# 2_DotexBoard_ENC28J60.net
KiCad netlist of a schematic drawn in Altium Designer
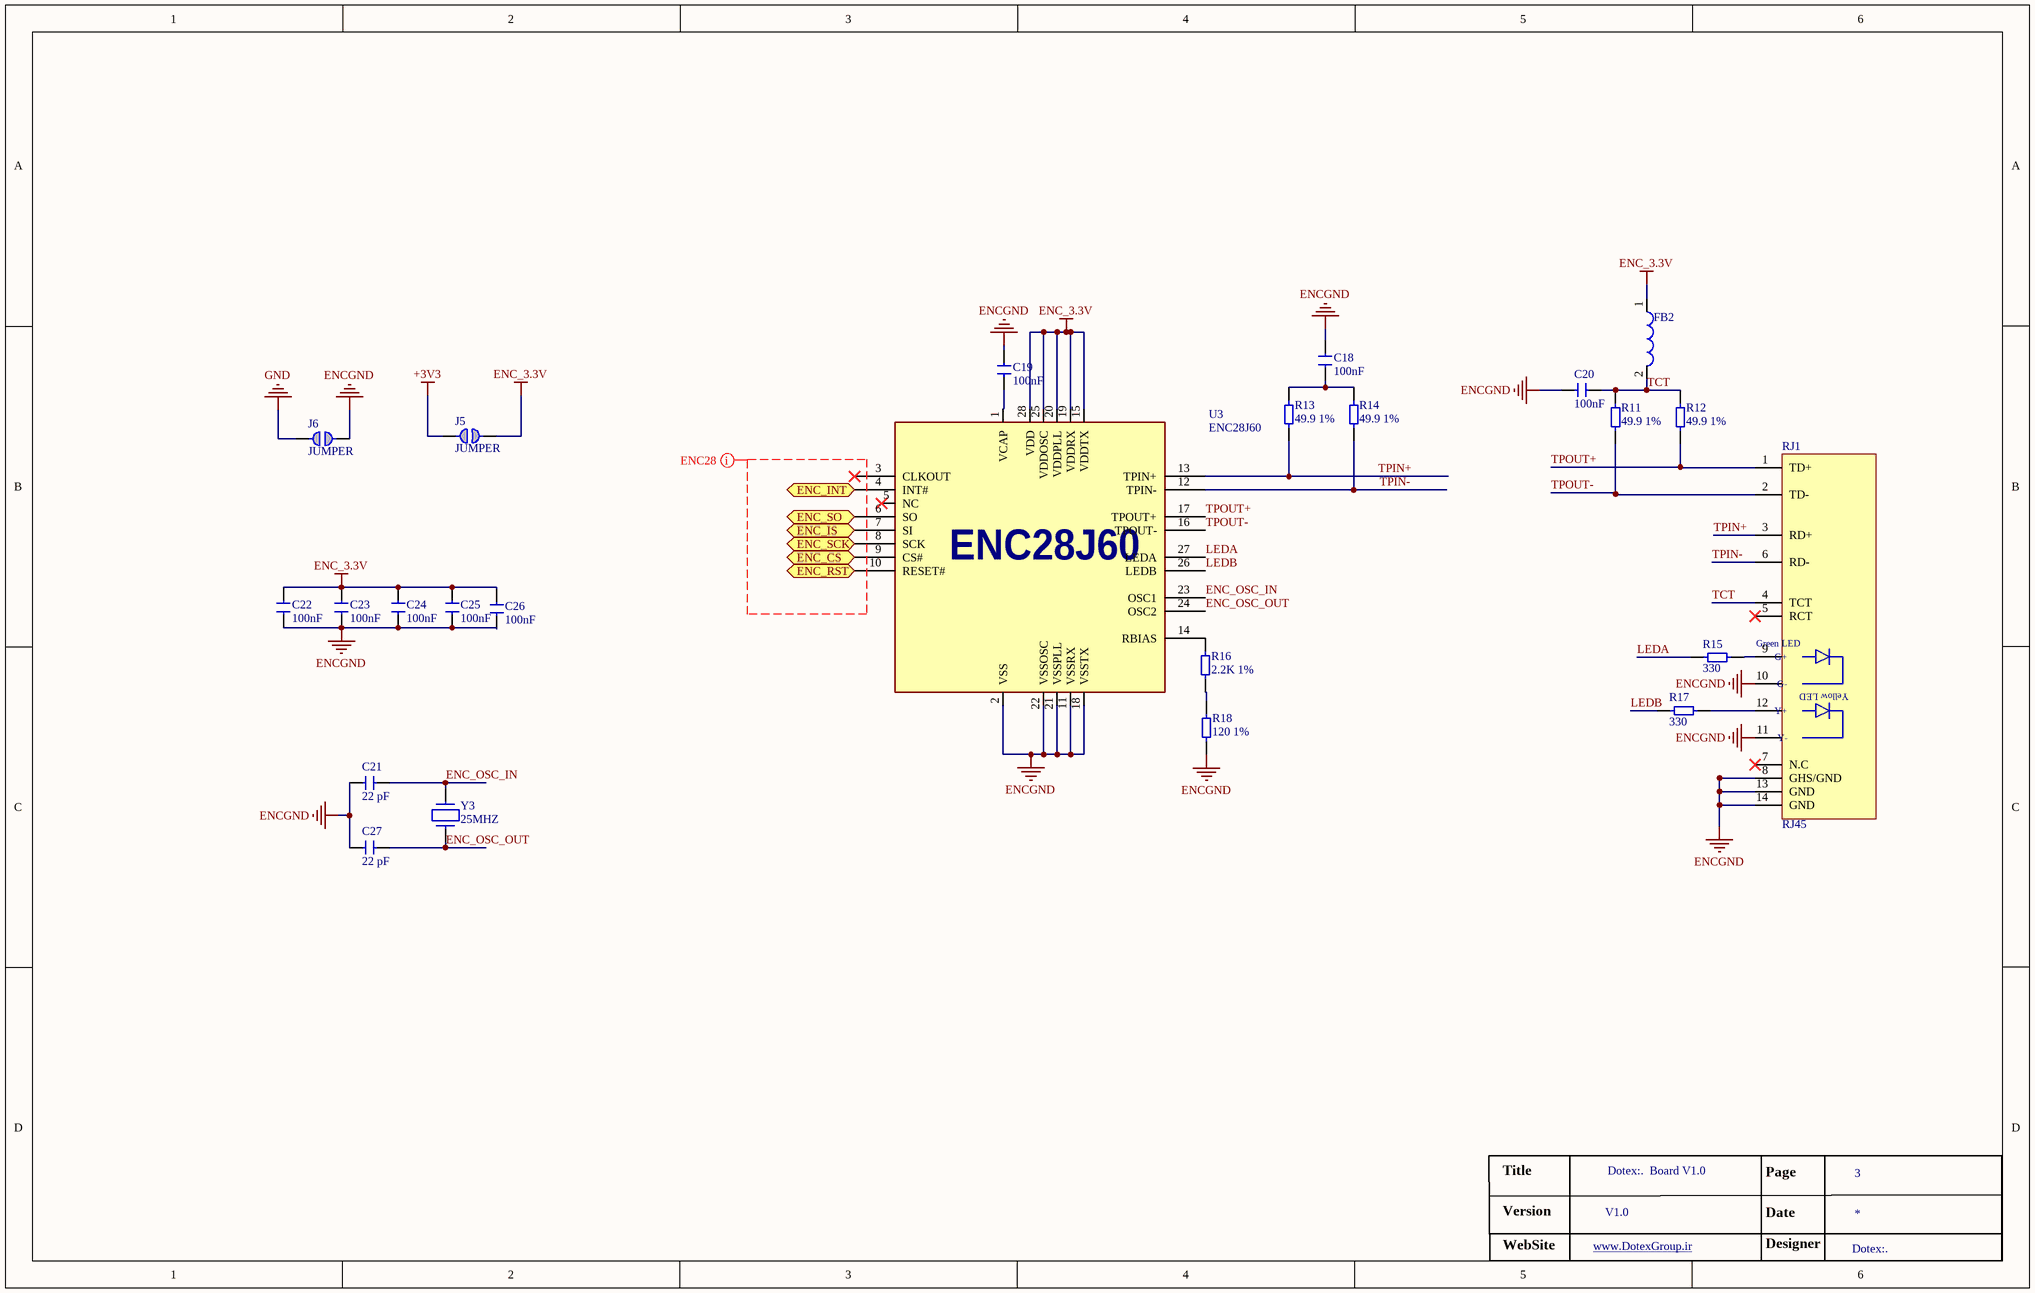
[diagram p0: [2]DotexBoard_ENC28J60.SchDoc]

(export (version "E")
  (design (tool "Eeschema 10.0.6"))
  (components
    (comp (ref "C18")
      (value "Comment")
      (footprint "0805 Capacitor")
      (fields (field (name "ALTIUM_UNNAMED_1") "100nF"))
      (libsource (lib "DotexGroup_LIB") (part "Capacitor SMD"))
    )
    (comp (ref "C19")
      (value "Comment")
      (footprint "0805 Capacitor")
      (fields (field (name "ALTIUM_UNNAMED_1") "100nF"))
      (libsource (lib "DotexGroup_LIB") (part "Capacitor SMD"))
    )
    (comp (ref "C20")
      (value "Comment")
      (footprint "0805 Capacitor")
      (fields (field (name "ALTIUM_UNNAMED_1") "100nF"))
      (libsource (lib "DotexGroup_LIB") (part "Capacitor SMD"))
    )
    (comp (ref "C21")
      (value "Comment")
      (footprint "0805 Capacitor")
      (fields (field (name "ALTIUM_UNNAMED_1") "22 pF"))
      (libsource (lib "DotexGroup_LIB") (part "Capacitor SMD"))
    )
    (comp (ref "C22")
      (value "Comment")
      (footprint "0805 Capacitor")
      (fields (field (name "ALTIUM_UNNAMED_1") "100nF"))
      (libsource (lib "DotexGroup_LIB") (part "Capacitor SMD"))
    )
    (comp (ref "C23")
      (value "Comment")
      (footprint "0805 Capacitor")
      (fields (field (name "ALTIUM_UNNAMED_1") "100nF"))
      (libsource (lib "DotexGroup_LIB") (part "Capacitor SMD"))
    )
    (comp (ref "C24")
      (value "Comment")
      (footprint "0805 Capacitor")
      (fields (field (name "ALTIUM_UNNAMED_1") "100nF"))
      (libsource (lib "DotexGroup_LIB") (part "Capacitor SMD"))
    )
    (comp (ref "C25")
      (value "Comment")
      (footprint "0805 Capacitor")
      (fields (field (name "ALTIUM_UNNAMED_1") "100nF"))
      (libsource (lib "DotexGroup_LIB") (part "Capacitor SMD"))
    )
    (comp (ref "C26")
      (value "Comment")
      (footprint "0805 Capacitor")
      (fields (field (name "ALTIUM_UNNAMED_1") "100nF"))
      (libsource (lib "DotexGroup_LIB") (part "Capacitor SMD"))
    )
    (comp (ref "C27")
      (value "Comment")
      (footprint "0805 Capacitor")
      (fields (field (name "ALTIUM_UNNAMED_1") "22 pF"))
      (libsource (lib "DotexGroup_LIB") (part "Capacitor SMD"))
    )
    (comp (ref "FB2")
      (value "Comment")
      (footprint "0805 Ferrit Bead")
      (libsource (lib "DotexGroup_LIB") (part "Ferrit Bead"))
    )
    (comp (ref "J5")
      (value "JUMPER")
      (footprint "0603 Resistor")
      (libsource (lib "DotexGroup_LIB") (part "jumper SMD"))
    )
    (comp (ref "J6")
      (value "JUMPER")
      (footprint "0603 Resistor")
      (libsource (lib "DotexGroup_LIB") (part "jumper SMD"))
    )
    (comp (ref "R11")
      (value "Comment")
      (footprint "0805 Resistor")
      (fields (field (name "ALTIUM_UNNAMED_1") "49.9 1%"))
      (libsource (lib "DotexGroup_LIB") (part "Resistor SMD"))
    )
    (comp (ref "R12")
      (value "Comment")
      (footprint "0805 Resistor")
      (fields (field (name "ALTIUM_UNNAMED_1") "49.9 1%"))
      (libsource (lib "DotexGroup_LIB") (part "Resistor SMD"))
    )
    (comp (ref "R13")
      (value "Comment")
      (footprint "0805 Resistor")
      (fields (field (name "ALTIUM_UNNAMED_1") "49.9 1%"))
      (libsource (lib "DotexGroup_LIB") (part "Resistor SMD"))
    )
    (comp (ref "R14")
      (value "Comment")
      (footprint "0805 Resistor")
      (fields (field (name "ALTIUM_UNNAMED_1") "49.9 1%"))
      (libsource (lib "DotexGroup_LIB") (part "Resistor SMD"))
    )
    (comp (ref "R15")
      (value "Comment")
      (footprint "0805 Resistor")
      (fields (field (name "ALTIUM_UNNAMED_1") "330"))
      (libsource (lib "DotexGroup_LIB") (part "Resistor SMD"))
    )
    (comp (ref "R16")
      (value "Comment")
      (footprint "0805 Resistor")
      (fields (field (name "ALTIUM_UNNAMED_1") "2.2K 1%"))
      (libsource (lib "DotexGroup_LIB") (part "Resistor SMD"))
    )
    (comp (ref "R17")
      (value "Comment")
      (footprint "0805 Resistor")
      (fields (field (name "ALTIUM_UNNAMED_1") "330"))
      (libsource (lib "DotexGroup_LIB") (part "Resistor SMD"))
    )
    (comp (ref "R18")
      (value "Comment")
      (footprint "0805 Resistor")
      (fields (field (name "ALTIUM_UNNAMED_1") "120 1%"))
      (libsource (lib "DotexGroup_LIB") (part "Resistor SMD"))
    )
    (comp (ref "RJ1")
      (value "RJ45")
      (footprint "HR91105A-RJ45")
      (libsource (lib "DotexGroup_LIB") (part "HR911105A"))
    )
    (comp (ref "U3")
      (value "ENC28J60")
      (footprint "SO_28_W")
      (description "Ethernet Controller, 10/100, MII/RMII")
      (fields (field (name "MANF") "Microchip") (field (name "MANF_P#") "ENC28J60-I/SO, ENC28J60-C/SO"))
      (libsource (lib "DotexGroup_LIB") (part "ENC28J60_SOP"))
    )
    (comp (ref "Y3") (value "25MHZ") (footprint "Xtal 2p") (libsource (lib "DotexGroup_LIB") (part "Xtal")))
  )
  (nets
    (net (code "1") (name "+3V3") (class "Default") (node (ref "J5") (pin "1") (pintype "passive")))
    (net (code "2") (name "/ENC_CS") (class "Default")
      (node (ref "U3") (pin "9") (pinfunction "CS#_9") (pintype "passive"))
    )
    (net (code "3") (name "/ENC_INT") (class "Default")
      (node (ref "U3") (pin "4") (pinfunction "INT#_4") (pintype "passive"))
    )
    (net (code "4") (name "/ENC_IS") (class "Default")
      (node (ref "U3") (pin "7") (pinfunction "SI_7") (pintype "passive"))
    )
    (net (code "5") (name "/ENC_OSC_IN") (class "Default")
      (node (ref "C21") (pin "2") (pintype "passive"))
      (node (ref "U3") (pin "23") (pinfunction "OSC1_23") (pintype "passive"))
      (node (ref "Y3") (pin "2") (pintype "passive"))
    )
    (net (code "6") (name "/ENC_OSC_OUT") (class "Default")
      (node (ref "C27") (pin "1") (pintype "passive"))
      (node (ref "U3") (pin "24") (pinfunction "OSC2_24") (pintype "passive"))
      (node (ref "Y3") (pin "1") (pintype "passive"))
    )
    (net (code "7") (name "/ENC_RST") (class "Default")
      (node (ref "U3") (pin "10") (pinfunction "RESET#_10") (pintype "passive"))
    )
    (net (code "8") (name "/ENC_SCK") (class "Default")
      (node (ref "U3") (pin "8") (pinfunction "SCK_8") (pintype "passive"))
    )
    (net (code "9") (name "/ENC_SO") (class "Default")
      (node (ref "U3") (pin "6") (pinfunction "SO_6") (pintype "passive"))
    )
    (net (code "10") (name "/LEDA") (class "Default")
      (node (ref "R15") (pin "1") (pintype "passive"))
      (node (ref "U3") (pin "27") (pinfunction "LEDA_27") (pintype "passive"))
    )
    (net (code "11") (name "/LEDB") (class "Default")
      (node (ref "R17") (pin "2") (pintype "passive"))
      (node (ref "U3") (pin "26") (pinfunction "LEDB_26") (pintype "passive"))
    )
    (net (code "12") (name "/TCT") (class "Default")
      (node (ref "C20") (pin "1") (pintype "passive"))
      (node (ref "FB2") (pin "2") (pinfunction "2_2") (pintype "passive"))
      (node (ref "R11") (pin "1") (pintype "passive"))
      (node (ref "R12") (pin "1") (pintype "passive"))
      (node (ref "RJ1") (pin "4") (pinfunction "TCT_4") (pintype "passive"))
    )
    (net (code "13") (name "/TPIN+") (class "Default")
      (node (ref "R13") (pin "2") (pintype "passive"))
      (node (ref "RJ1") (pin "3") (pinfunction "RD+_3") (pintype "passive"))
      (node (ref "U3") (pin "13") (pinfunction "TPIN+_13") (pintype "passive"))
    )
    (net (code "14") (name "/TPIN-") (class "Default")
      (node (ref "R14") (pin "2") (pintype "passive"))
      (node (ref "RJ1") (pin "6") (pinfunction "RD-_6") (pintype "passive"))
      (node (ref "U3") (pin "12") (pinfunction "TPIN-_12") (pintype "passive"))
    )
    (net (code "15") (name "/TPOUT+") (class "Default")
      (node (ref "R12") (pin "2") (pintype "passive"))
      (node (ref "RJ1") (pin "1") (pinfunction "TD+_1") (pintype "passive"))
      (node (ref "U3") (pin "17") (pinfunction "TPOUT+_17") (pintype "passive"))
    )
    (net (code "16") (name "/TPOUT-") (class "Default")
      (node (ref "R11") (pin "2") (pintype "passive"))
      (node (ref "RJ1") (pin "2") (pinfunction "TD-_2") (pintype "passive"))
      (node (ref "U3") (pin "16") (pinfunction "TPOUT-_16") (pintype "passive"))
    )
    (net (code "17") (name "ENCGND") (class "Default")
      (node (ref "C18") (pin "1") (pintype "passive"))
      (node (ref "C19") (pin "2") (pintype "passive"))
      (node (ref "C20") (pin "2") (pintype "passive"))
      (node (ref "C21") (pin "1") (pintype "passive"))
      (node (ref "C22") (pin "1") (pintype "passive"))
      (node (ref "C23") (pin "1") (pintype "passive"))
      (node (ref "C24") (pin "1") (pintype "passive"))
      (node (ref "C25") (pin "1") (pintype "passive"))
      (node (ref "C26") (pin "1") (pintype "passive"))
      (node (ref "C27") (pin "2") (pintype "passive"))
      (node (ref "J6") (pin "2") (pintype "passive"))
      (node (ref "R18") (pin "2") (pintype "passive"))
      (node (ref "RJ1") (pin "10") (pintype "passive"))
      (node (ref "RJ1") (pin "11") (pintype "passive"))
      (node (ref "RJ1") (pin "13") (pinfunction "GND_13") (pintype "passive"))
      (node (ref "RJ1") (pin "14") (pinfunction "GND_14") (pintype "passive"))
      (node (ref "RJ1") (pin "8") (pinfunction "GHS/GND_8") (pintype "passive"))
      (node (ref "U3") (pin "11") (pinfunction "VSSRX_11") (pintype "passive"))
      (node (ref "U3") (pin "18") (pinfunction "VSSTX_18") (pintype "passive"))
      (node (ref "U3") (pin "2") (pinfunction "VSS_2") (pintype "passive"))
      (node (ref "U3") (pin "21") (pinfunction "VSSPLL_21") (pintype "passive"))
      (node (ref "U3") (pin "22") (pinfunction "VSSOSC_22") (pintype "passive"))
    )
    (net (code "18") (name "ENC_3.3V") (class "Default")
      (node (ref "C22") (pin "2") (pintype "passive"))
      (node (ref "C23") (pin "2") (pintype "passive"))
      (node (ref "C24") (pin "2") (pintype "passive"))
      (node (ref "C25") (pin "2") (pintype "passive"))
      (node (ref "C26") (pin "2") (pintype "passive"))
      (node (ref "FB2") (pin "1") (pinfunction "1_1") (pintype "passive"))
      (node (ref "J5") (pin "2") (pintype "passive"))
      (node (ref "U3") (pin "15") (pinfunction "VDDTX_15") (pintype "passive"))
      (node (ref "U3") (pin "19") (pinfunction "VDDRX_19") (pintype "passive"))
      (node (ref "U3") (pin "20") (pinfunction "VDDPLL_20") (pintype "passive"))
      (node (ref "U3") (pin "25") (pinfunction "VDDOSC_25") (pintype "passive"))
      (node (ref "U3") (pin "28") (pinfunction "VDD_28") (pintype "passive"))
    )
    (net (code "19") (name "GND") (class "Default") (node (ref "J6") (pin "1") (pintype "passive")))
    (net (code "20") (name "Net-(C18-Pad2)") (class "Default")
      (node (ref "C18") (pin "2") (pintype "passive"))
      (node (ref "R13") (pin "1") (pintype "passive"))
      (node (ref "R14") (pin "1") (pintype "passive"))
    )
    (net (code "21") (name "Net-(R15-Pad2)") (class "Default")
      (node (ref "R15") (pin "2") (pintype "passive"))
      (node (ref "RJ1") (pin "9") (pintype "passive"))
    )
    (net (code "22") (name "Net-(R16-Pad2)") (class "Default")
      (node (ref "R16") (pin "2") (pintype "passive"))
      (node (ref "R18") (pin "1") (pintype "passive"))
    )
    (net (code "23") (name "Net-(R17-Pad1)") (class "Default")
      (node (ref "R17") (pin "1") (pintype "passive"))
      (node (ref "RJ1") (pin "12") (pintype "passive"))
    )
    (net (code "24") (name "Net-(U3-RBIAS)") (class "Default")
      (node (ref "R16") (pin "1") (pintype "passive"))
      (node (ref "U3") (pin "14") (pinfunction "RBIAS_14") (pintype "passive"))
    )
    (net (code "25") (name "Net-(U3-VCAP)") (class "Default")
      (node (ref "C19") (pin "1") (pintype "passive"))
      (node (ref "U3") (pin "1") (pinfunction "VCAP_1") (pintype "passive"))
    )
    (net (code "26") (name "unconnected-(RJ1-N.C-Pad7)") (class "Default")
      (node (ref "RJ1") (pin "7") (pinfunction "N.C_7") (pintype "passive+no_connect"))
    )
    (net (code "27") (name "unconnected-(RJ1-RCT-Pad5)") (class "Default")
      (node (ref "RJ1") (pin "5") (pinfunction "RCT_5") (pintype "passive+no_connect"))
    )
    (net (code "28") (name "unconnected-(U3-CLKOUT-Pad3)") (class "Default")
      (node (ref "U3") (pin "3") (pinfunction "CLKOUT_3") (pintype "passive+no_connect"))
    )
    (net (code "29") (name "unconnected-(U3-NC-Pad5)") (class "Default")
      (node (ref "U3") (pin "5") (pinfunction "NC_5") (pintype "passive+no_connect"))
    )
  )
)
